# High-Side_Driver.net
KiCad netlist of a schematic drawn in Altium Designer
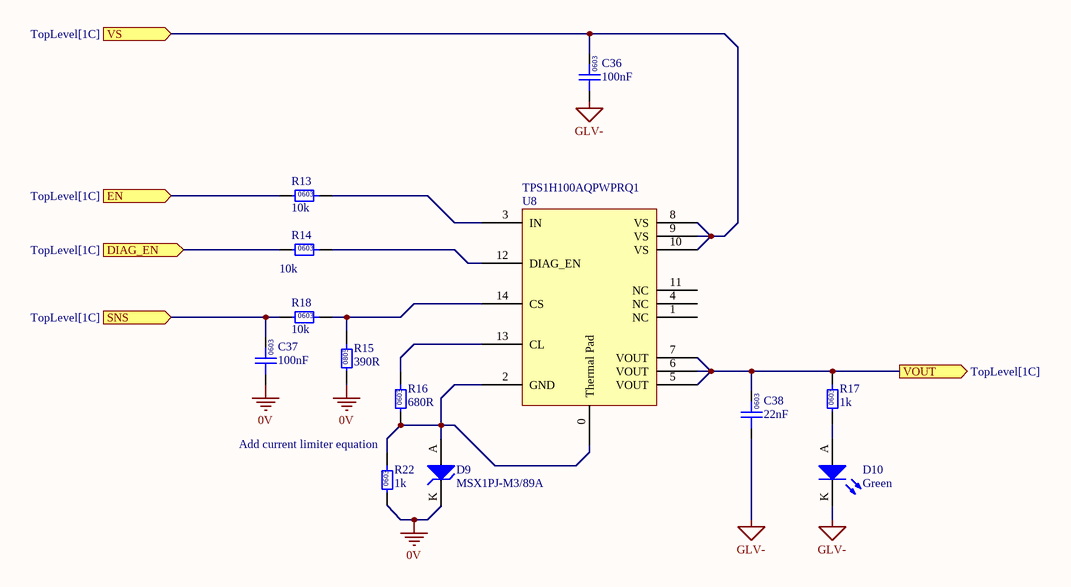
[diagram p0: High-Side Driver.SchDoc]

(export (version "E")
  (design (tool "Eeschema 10.0.6"))
  (components
    (comp (ref "C36")
      (value "100nF")
      (footprint "0603")
      (fields
        (field (name "PART NUMBER") "GCM188L81H104KA57D")
        (field (name "MANUFACTURER") "muRata")
        (field (name "TOLERANCE") "±10%")
      )
      (libsource (lib "ts_standard_library") (part "Capacitor 0603"))
    )
    (comp (ref "C37")
      (value "100nF")
      (footprint "0603")
      (fields
        (field (name "PART NUMBER") "GCM188L81H104KA57D")
        (field (name "MANUFACTURER") "muRata")
        (field (name "TOLERANCE") "±10%")
      )
      (libsource (lib "ts_standard_library") (part "Capacitor 0603"))
    )
    (comp (ref "C38")
      (value "22nF")
      (footprint "0603")
      (fields
        (field (name "PART NUMBER") "GCM188R71H223KA37J")
        (field (name "MANUFACTURER") "Murata Electronics")
        (field (name "TOLERANCE") "±10%")
      )
      (libsource (lib "ts_standard_library") (part "Capacitor 0603"))
    )
    (comp (ref "D9")
      (value "MSX1PJ-M3/89A")
      (footprint "VISHAY DO-219")
      (fields (field (name "MANUFACTURER") "Vishay General Semiconductor - Diodes Division"))
      (libsource (lib "ts_standard_library") (part "Zener Diode"))
    )
    (comp (ref "D10")
      (value "Green")
      (footprint "0805 LED")
      (description "Green LED Indication - Discrete 1.75V 0805 (2012 Metric)")
      (fields (field (name "PART NUMBER") "SML-210FTT86") (field (name "MANUFACTURER") "ROHM Semiconductor"))
      (libsource (lib "ts_standard_library") (part "LED"))
    )
    (comp (ref "R13")
      (value "10k")
      (footprint "0603")
      (fields
        (field (name "PART NUMBER") "RC0603FR-0710KL")
        (field (name "MANUFACTURER") "YAGEO")
        (field (name "TOLERANCE") "0.01")
      )
      (libsource (lib "ts_standard_library") (part "Resistor 0603"))
    )
    (comp (ref "R14")
      (value "10k")
      (footprint "0603")
      (fields
        (field (name "PART NUMBER") "RC0603FR-0710KL")
        (field (name "MANUFACTURER") "YAGEO")
        (field (name "TOLERANCE") "0.01")
      )
      (libsource (lib "ts_standard_library") (part "Resistor 0603"))
    )
    (comp (ref "R15")
      (value "390R")
      (footprint "0805")
      (fields
        (field (name "PART NUMBER") "RC0805FR07390RL")
        (field (name "MANUFACTURER") "YAGEO")
        (field (name "TOLERANCE") "0.01")
      )
      (libsource (lib "ts_standard_library") (part "Resistor 0805"))
    )
    (comp (ref "R16")
      (value "680R")
      (footprint "0603")
      (fields
        (field (name "PART NUMBER") "RC0603JR-13680RL")
        (field (name "MANUFACTURER") "YAGEO")
        (field (name "TOLERANCE") "0.01")
      )
      (libsource (lib "ts_standard_library") (part "Resistor 0603"))
    )
    (comp (ref "R17")
      (value "1k")
      (footprint "0603")
      (fields
        (field (name "PART NUMBER") "RC0603FR-071KL")
        (field (name "MANUFACTURER") "YAGEO")
        (field (name "TOLERANCE") "0.01")
      )
      (libsource (lib "ts_standard_library") (part "Resistor 0603"))
    )
    (comp (ref "R18")
      (value "10k")
      (footprint "0603")
      (fields
        (field (name "PART NUMBER") "RC0603FR-0710KL")
        (field (name "MANUFACTURER") "YAGEO")
        (field (name "TOLERANCE") "0.01")
      )
      (libsource (lib "ts_standard_library") (part "Resistor 0603"))
    )
    (comp (ref "R22")
      (value "1k")
      (footprint "0603")
      (fields
        (field (name "PART NUMBER") "RC0603FR-071KL")
        (field (name "MANUFACTURER") "YAGEO")
        (field (name "TOLERANCE") "0.01")
      )
      (libsource (lib "ts_standard_library") (part "Resistor 0603"))
    )
    (comp (ref "U8")
      (value "TPS1H100AQPWPRQ1")
      (footprint "TI_14_TSSOP")
      (description "IC PWR SWTCH N-CHAN 1:1 14HTSSOP")
      (fields (field (name "MANUFACTURER") "Texas Instruments"))
      (libsource (lib "ts_standard_library") (part "TPS1H100AQPWPRQ1"))
    )
  )
  (nets
    (net (code "1") (name "/DIAG_EN") (class "Default")
      (node (ref "R14") (pin "1") (pinfunction "1_1") (pintype "passive"))
    )
    (net (code "2") (name "/EN") (class "Default")
      (node (ref "R13") (pin "1") (pinfunction "1_1") (pintype "passive"))
    )
    (net (code "3") (name "/SNS") (class "Default")
      (node (ref "C37") (pin "2") (pinfunction "2_2") (pintype "passive"))
      (node (ref "R18") (pin "1") (pinfunction "1_1") (pintype "passive"))
    )
    (net (code "4") (name "/VOUT") (class "Default")
      (node (ref "C38") (pin "2") (pinfunction "2_2") (pintype "passive"))
      (node (ref "R17") (pin "2") (pinfunction "2_2") (pintype "passive"))
      (node (ref "U8") (pin "5") (pinfunction "VOUT_5") (pintype "passive"))
      (node (ref "U8") (pin "6") (pinfunction "VOUT_6") (pintype "passive"))
      (node (ref "U8") (pin "7") (pinfunction "VOUT_7") (pintype "passive"))
    )
    (net (code "5") (name "/VS") (class "Default")
      (node (ref "C36") (pin "2") (pinfunction "2_2") (pintype "passive"))
      (node (ref "U8") (pin "10") (pinfunction "VS_10") (pintype "passive"))
      (node (ref "U8") (pin "8") (pinfunction "VS_8") (pintype "passive"))
      (node (ref "U8") (pin "9") (pinfunction "VS_9") (pintype "passive"))
    )
    (net (code "6") (name "0V") (class "Default")
      (node (ref "C37") (pin "1") (pinfunction "1_1") (pintype "passive"))
      (node (ref "D9") (pin "K") (pinfunction "K_K") (pintype "passive"))
      (node (ref "R15") (pin "1") (pinfunction "1_1") (pintype "passive"))
      (node (ref "R22") (pin "1") (pinfunction "1_1") (pintype "passive"))
    )
    (net (code "7") (name "GLV-") (class "Default")
      (node (ref "C36") (pin "1") (pinfunction "1_1") (pintype "passive"))
      (node (ref "C38") (pin "1") (pinfunction "1_1") (pintype "passive"))
      (node (ref "D10") (pin "K") (pinfunction "K_K") (pintype "passive"))
    )
    (net (code "8") (name "Net-(D10-PadA)") (class "Default")
      (node (ref "D10") (pin "A") (pinfunction "A_A") (pintype "passive"))
      (node (ref "R17") (pin "1") (pinfunction "1_1") (pintype "passive"))
    )
    (net (code "9") (name "Net-(U8-CL)") (class "Default")
      (node (ref "R16") (pin "2") (pinfunction "2_2") (pintype "passive"))
      (node (ref "U8") (pin "13") (pinfunction "CL_13") (pintype "passive"))
    )
    (net (code "10") (name "Net-(U8-CS)") (class "Default")
      (node (ref "R15") (pin "2") (pinfunction "2_2") (pintype "passive"))
      (node (ref "R18") (pin "2") (pinfunction "2_2") (pintype "passive"))
      (node (ref "U8") (pin "14") (pinfunction "CS_14") (pintype "passive"))
    )
    (net (code "11") (name "Net-(U8-DIAG_EN)") (class "Default")
      (node (ref "R14") (pin "2") (pinfunction "2_2") (pintype "passive"))
      (node (ref "U8") (pin "12") (pinfunction "DIAG_EN_12") (pintype "passive"))
    )
    (net (code "12") (name "Net-(U8-GND)") (class "Default")
      (node (ref "D9") (pin "A") (pinfunction "A_A") (pintype "passive"))
      (node (ref "R16") (pin "1") (pinfunction "1_1") (pintype "passive"))
      (node (ref "R22") (pin "2") (pinfunction "2_2") (pintype "passive"))
      (node (ref "U8") (pin "0") (pinfunction "Thermal_Pad_0") (pintype "passive"))
      (node (ref "U8") (pin "2") (pinfunction "GND_2") (pintype "passive"))
    )
    (net (code "13") (name "Net-(U8-IN)") (class "Default")
      (node (ref "R13") (pin "2") (pinfunction "2_2") (pintype "passive"))
      (node (ref "U8") (pin "3") (pinfunction "IN_3") (pintype "passive"))
    )
    (net (code "14") (name "unconnected-(U8-NC-Pad1)") (class "Default")
      (node (ref "U8") (pin "1") (pinfunction "NC_1") (pintype "passive"))
    )
    (net (code "15") (name "unconnected-(U8-NC-Pad4)") (class "Default")
      (node (ref "U8") (pin "4") (pinfunction "NC_4") (pintype "passive"))
    )
    (net (code "16") (name "unconnected-(U8-NC-Pad11)") (class "Default")
      (node (ref "U8") (pin "11") (pinfunction "NC_11") (pintype "passive"))
    )
  )
)
